# MCU.net
KiCad netlist of a schematic drawn in Altium Designer
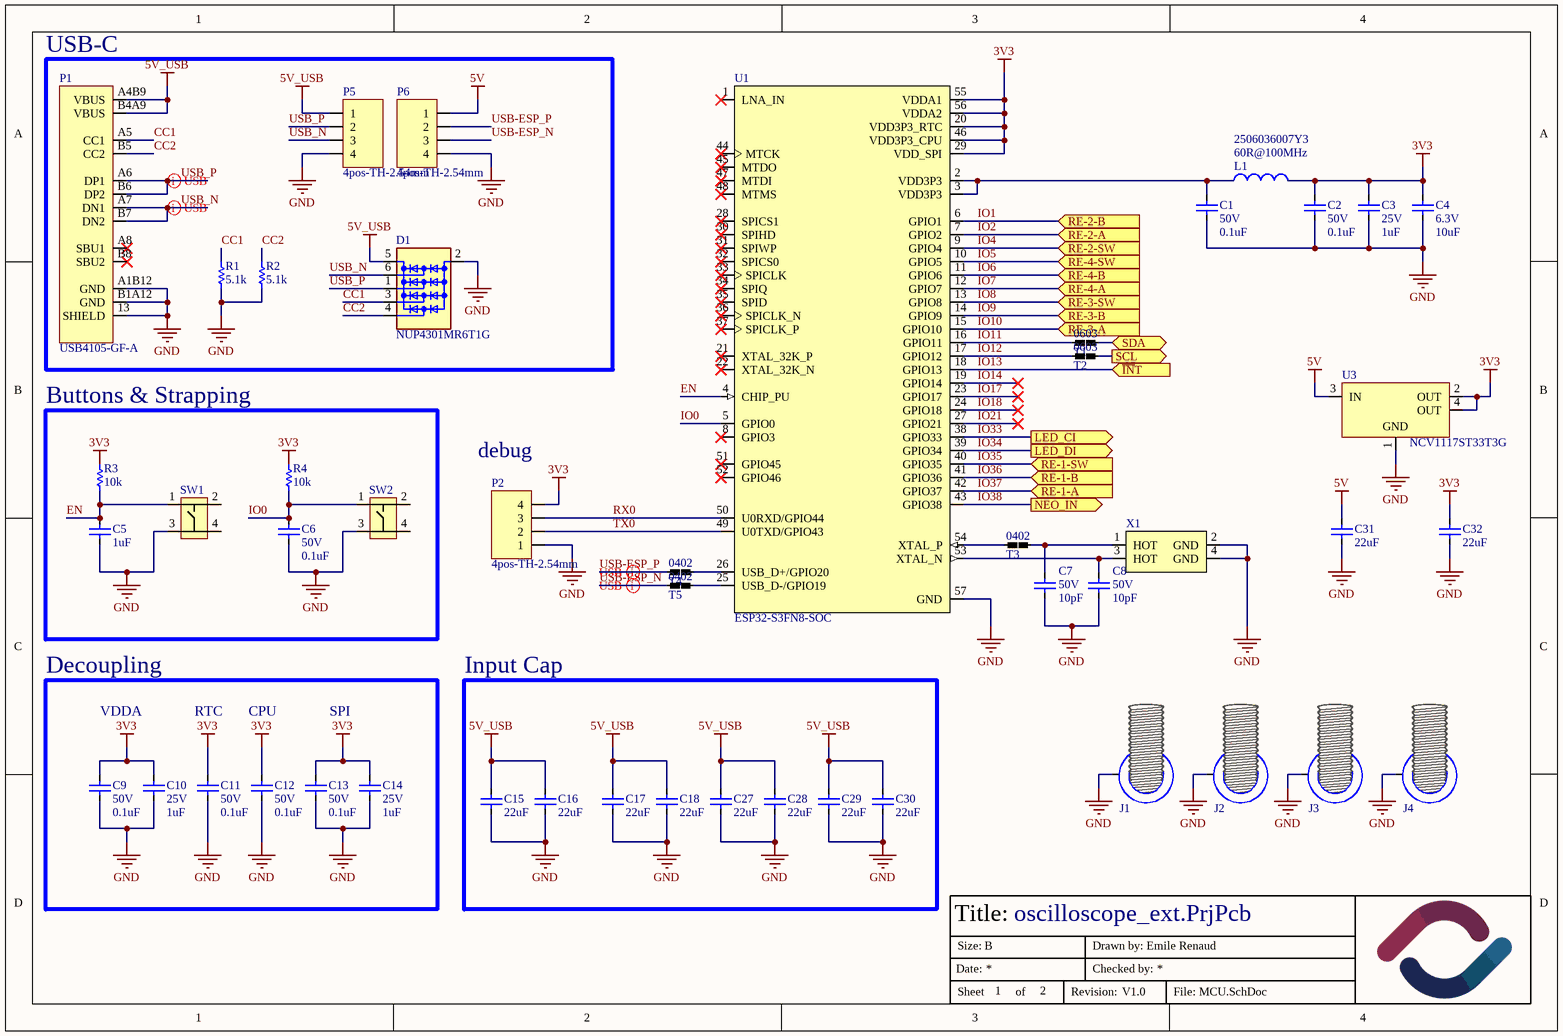
[diagram p0: MCU.SchDoc]

(export (version "E")
  (design (tool "Eeschema 10.0.6"))
  (components
    (comp (ref "C1")
      (value "0.1uF")
      (footprint "CAPACITOR-0603")
      (description "Capacitor-0603-0.1uF-50V-X7R")
      (fields (field (name "VOLT") "50V"))
      (libsource (lib "Capacitors") (part "Capacitor-0603-0.1uF-50V-X7R"))
    )
    (comp (ref "C2")
      (value "0.1uF")
      (footprint "CAPACITOR-0603")
      (description "Capacitor-0603-0.1uF-50V-X7R")
      (fields (field (name "VOLT") "50V"))
      (libsource (lib "Capacitors") (part "Capacitor-0603-0.1uF-50V-X7R"))
    )
    (comp (ref "C3")
      (value "1uF")
      (footprint "CAPACITOR-0603")
      (description "Capacitor-0603-1uF-25V-X5R")
      (fields (field (name "VOLT") "25V"))
      (libsource (lib "Capacitors") (part "Capacitor-0603-1uF-25V-X5R"))
    )
    (comp (ref "C4")
      (value "10uF")
      (footprint "CAPACITOR-0603")
      (description "Capacitor-0603-10uF-6.3V-X5R, Low ESR, Low ESL")
      (fields (field (name "VOLT") "6.3V") (field (name "Comment") "Capacitor-0603-10uF-6.3V-X5R"))
      (libsource (lib "Capacitors") (part "Capacitor-0603-10uF-6.3V-X5R"))
    )
    (comp (ref "C5")
      (value "1uF")
      (footprint "CAPACITOR-0603")
      (description "Capacitor-0603-1uF-25V-X5R")
      (libsource (lib "Capacitors") (part "Capacitor-0603-1uF-25V-X5R"))
    )
    (comp (ref "C6")
      (value "0.1uF")
      (footprint "CAPACITOR-0603")
      (description "Capacitor-0603-0.1uF-50V-X7R")
      (fields (field (name "VOLT") "50V"))
      (libsource (lib "Capacitors") (part "Capacitor-0603-0.1uF-50V-X7R"))
    )
    (comp (ref "C7")
      (value "10pF")
      (footprint "CAPACITOR-0402")
      (description "Capacitor-0402-10pF-50V-C0G")
      (fields (field (name "VOLT") "50V"))
      (libsource (lib "Capacitors") (part "Capacitor-0402-10pF-50V-C0G"))
    )
    (comp (ref "C8")
      (value "10pF")
      (footprint "CAPACITOR-0402")
      (description "Capacitor-0402-10pF-50V-C0G")
      (fields (field (name "VOLT") "50V"))
      (libsource (lib "Capacitors") (part "Capacitor-0402-10pF-50V-C0G"))
    )
    (comp (ref "C9")
      (value "0.1uF")
      (footprint "CAPACITOR-0603")
      (description "Capacitor-0603-0.1uF-50V-X7R")
      (fields (field (name "VOLT") "50V"))
      (libsource (lib "Capacitors") (part "Capacitor-0603-0.1uF-50V-X7R"))
    )
    (comp (ref "C10")
      (value "1uF")
      (footprint "CAPACITOR-0603")
      (description "Capacitor-0603-1uF-25V-X5R")
      (fields (field (name "VOLT") "25V"))
      (libsource (lib "Capacitors") (part "Capacitor-0603-1uF-25V-X5R"))
    )
    (comp (ref "C11")
      (value "0.1uF")
      (footprint "CAPACITOR-0603")
      (description "Capacitor-0603-0.1uF-50V-X7R")
      (fields (field (name "VOLT") "50V"))
      (libsource (lib "Capacitors") (part "Capacitor-0603-0.1uF-50V-X7R"))
    )
    (comp (ref "C12")
      (value "0.1uF")
      (footprint "CAPACITOR-0603")
      (description "Capacitor-0603-0.1uF-50V-X7R")
      (fields (field (name "VOLT") "50V"))
      (libsource (lib "Capacitors") (part "Capacitor-0603-0.1uF-50V-X7R"))
    )
    (comp (ref "C13")
      (value "0.1uF")
      (footprint "CAPACITOR-0603")
      (description "Capacitor-0603-0.1uF-50V-X7R")
      (fields (field (name "VOLT") "50V"))
      (libsource (lib "Capacitors") (part "Capacitor-0603-0.1uF-50V-X7R"))
    )
    (comp (ref "C14")
      (value "1uF")
      (footprint "CAPACITOR-0603")
      (description "Capacitor-0603-1uF-25V-X5R")
      (fields (field (name "VOLT") "25V"))
      (libsource (lib "Capacitors") (part "Capacitor-0603-1uF-25V-X5R"))
    )
    (comp (ref "C15")
      (value "22uF")
      (footprint "CAPACITOR-0805")
      (description "Capacitor-0805-22uF-16V-X5R")
      (libsource (lib "Capacitors") (part "Capacitor-0805-22uF-16V-X5R"))
    )
    (comp (ref "C16")
      (value "22uF")
      (footprint "CAPACITOR-0805")
      (description "Capacitor-0805-22uF-16V-X5R")
      (libsource (lib "Capacitors") (part "Capacitor-0805-22uF-16V-X5R"))
    )
    (comp (ref "C17")
      (value "22uF")
      (footprint "CAPACITOR-0805")
      (description "Capacitor-0805-22uF-16V-X5R")
      (libsource (lib "Capacitors") (part "Capacitor-0805-22uF-16V-X5R"))
    )
    (comp (ref "C18")
      (value "22uF")
      (footprint "CAPACITOR-0805")
      (description "Capacitor-0805-22uF-16V-X5R")
      (libsource (lib "Capacitors") (part "Capacitor-0805-22uF-16V-X5R"))
    )
    (comp (ref "C27")
      (value "22uF")
      (footprint "CAPACITOR-0805")
      (description "Capacitor-0805-22uF-16V-X5R")
      (libsource (lib "Capacitors") (part "Capacitor-0805-22uF-16V-X5R"))
    )
    (comp (ref "C28")
      (value "22uF")
      (footprint "CAPACITOR-0805")
      (description "Capacitor-0805-22uF-16V-X5R")
      (libsource (lib "Capacitors") (part "Capacitor-0805-22uF-16V-X5R"))
    )
    (comp (ref "C29")
      (value "22uF")
      (footprint "CAPACITOR-0805")
      (description "Capacitor-0805-22uF-16V-X5R")
      (libsource (lib "Capacitors") (part "Capacitor-0805-22uF-16V-X5R"))
    )
    (comp (ref "C30")
      (value "22uF")
      (footprint "CAPACITOR-0805")
      (description "Capacitor-0805-22uF-16V-X5R")
      (libsource (lib "Capacitors") (part "Capacitor-0805-22uF-16V-X5R"))
    )
    (comp (ref "C31")
      (value "22uF")
      (footprint "CAPACITOR-0805")
      (description "Capacitor-0805-22uF-16V-X5R")
      (libsource (lib "Capacitors") (part "Capacitor-0805-22uF-16V-X5R"))
    )
    (comp (ref "C32")
      (value "22uF")
      (footprint "CAPACITOR-0805")
      (description "Capacitor-0805-22uF-16V-X5R")
      (libsource (lib "Capacitors") (part "Capacitor-0805-22uF-16V-X5R"))
    )
    (comp (ref "D1")
      (value "NUP4301MR6T1G")
      (footprint "SOT-23-6")
      (description "4CH Clamp Ipp Tvs Diode Surface Mount SOT23-6 (SC74)")
      (libsource (lib "diodes") (part "NUP4301MR6T1G"))
    )
    (comp (ref "J1")
      (value "hole")
      (footprint "HOLE-3.40MM-M3-8MMEYELET")
      (description "Hole for M3 Bolt with 8mm pad")
      (libsource (lib "JumpersAndHoles") (part "Hole 3.40mm M3-Eyelet"))
    )
    (comp (ref "J2")
      (value "hole")
      (footprint "HOLE-3.40MM-M3-8MMEYELET")
      (description "Hole for M3 Bolt with 8mm pad")
      (libsource (lib "JumpersAndHoles") (part "Hole 3.40mm M3-Eyelet"))
    )
    (comp (ref "J3")
      (value "hole")
      (footprint "HOLE-3.40MM-M3-8MMEYELET")
      (description "Hole for M3 Bolt with 8mm pad")
      (libsource (lib "JumpersAndHoles") (part "Hole 3.40mm M3-Eyelet"))
    )
    (comp (ref "J4")
      (value "hole")
      (footprint "HOLE-3.40MM-M3-8MMEYELET")
      (description "Hole for M3 Bolt with 8mm pad")
      (libsource (lib "JumpersAndHoles") (part "Hole 3.40mm M3-Eyelet"))
    )
    (comp (ref "L1")
      (value "2506036007Y3")
      (footprint "CAPACITOR-0603")
      (description "60 Ohms @ 100 MHz 1 Signal Line Ferrite Bead 0603 (1608 Metric) 3A 40mOhm")
      (fields (field (name "ALTIUM_VALUE") "60R@100MHz"))
      (libsource (lib "Inductors") (part "2506036007Y3"))
    )
    (comp (ref "P1")
      (value "USB4105-GF-A")
      (footprint "USB-C")
      (description "CONN RCP USB2.0 TYP C 24P SMD RA\r\n5A")
      (libsource (lib "PC-connector") (part "USB4105-GF-A"))
    )
    (comp (ref "P2")
      (value "4pos-TH-2.54mm")
      (footprint "HDR1X4")
      (description "4pos TH 2.54mm Header")
      (libsource (lib "") (part "4pos-TH-2.54mm_1"))
    )
    (comp (ref "P5")
      (value "4pos-TH-2.54mm")
      (footprint "HDR1X4")
      (description "4pos TH 2.54mm Header")
      (libsource (lib "Header") (part "4pos-TH-2.54mm"))
    )
    (comp (ref "P6")
      (value "4pos-TH-2.54mm")
      (footprint "HDR1X4")
      (description "4pos TH 2.54mm Header")
      (libsource (lib "") (part "4pos-TH-2.54mm_2"))
    )
    (comp (ref "R1")
      (value "5.1k")
      (footprint "RESISTOR-0603")
      (description "0603 footprint DO NOT INSTALL")
      (fields (field (name "Comment") "Resistor-0603-5.1k"))
      (libsource (lib "Resistors") (part "Resistor-0603-DNI"))
    )
    (comp (ref "R2")
      (value "5.1k")
      (footprint "RESISTOR-0603")
      (description "0603 footprint DO NOT INSTALL")
      (fields (field (name "Comment") "Resistor-0603-5.1k"))
      (libsource (lib "Resistors") (part "Resistor-0603-DNI"))
    )
    (comp (ref "R3")
      (value "10k")
      (footprint "Resistor-0603")
      (description "Resistor0603-10k")
      (fields (field (name "Comment") "SMT resistor"))
      (libsource (lib "Resistors") (part "Resistor0603-10k"))
    )
    (comp (ref "R4")
      (value "10k")
      (footprint "Resistor-0603")
      (description "Resistor0603-10k")
      (fields (field (name "Comment") "SMT resistor"))
      (libsource (lib "Resistors") (part "Resistor0603-10k"))
    )
    (comp (ref "SW1")
      (value "PTS815 SJM 250 SMTR LFS")
      (footprint "SW4_PTS815 SJM 250 SMTR LFS_CNK")
      (description "TACT 4.2 X 3.2, 2.5 MM H, 180GF,")
      (libsource (lib "THTPushButtonSwitches") (part "PTS815 SJM 250 SMTR LFS"))
    )
    (comp (ref "SW2")
      (value "PTS815 SJM 250 SMTR LFS")
      (footprint "SW4_PTS815 SJM 250 SMTR LFS_CNK")
      (description "TACT 4.2 X 3.2, 2.5 MM H, 180GF,")
      (libsource (lib "THTPushButtonSwitches") (part "PTS815 SJM 250 SMTR LFS"))
    )
    (comp (ref "T1")
      (value "NetTie_0603")
      (footprint "NetTie-0603-short")
      (libsource (lib "JumpersAndHoles") (part "NetTie_0603"))
    )
    (comp (ref "T2")
      (value "NetTie_0603")
      (footprint "NetTie-0603-short")
      (libsource (lib "JumpersAndHoles") (part "NetTie_0603"))
    )
    (comp (ref "T3")
      (value "NetTie_0402")
      (footprint "NetTie-0402")
      (libsource (lib "JumpersAndHoles") (part "NetTie_0402"))
    )
    (comp (ref "T4")
      (value "NetTie_0402")
      (footprint "NetTie-0402")
      (libsource (lib "JumpersAndHoles") (part "NetTie_0402"))
    )
    (comp (ref "T5")
      (value "NetTie_0402")
      (footprint "NetTie-0402")
      (libsource (lib "JumpersAndHoles") (part "NetTie_0402"))
    )
    (comp (ref "U1")
      (value "ESP32-S3FN8-SOC")
      (footprint "VFQFN-56 Exposed Pad")
      (fields (field (name "MF") "Espressif Systems") (field (name "MP") "ESP32-S3FN8"))
      (libsource (lib "Microcontrollers") (part "ESP32-S3FN8-SOC"))
    )
    (comp (ref "U3")
      (value "NCV1117ST33T3G")
      (footprint "SOT-223-3/TO-261-3S")
      (description "IC REG LINEAR 3.3V 1A SOT223")
      (libsource (lib "PMIC-VoltageRegulators-LinearRegulators") (part "NCV1117ST33T3G"))
    )
    (comp (ref "X1")
      (value "CX2016DB40000D0FLJCC")
      (footprint "4-SMD")
      (description "40 MHz ±10ppm Crystal 8pF 50 Ohms 4-SMD, No Lead")
      (libsource (lib "Crystals") (part "CX2016DB40000D0FLJCC"))
    )
  )
  (nets
    (net (code "1") (name "/CC1") (class "Default")
      (node (ref "D1") (pin "3") (pinfunction "L3_3") (pintype "passive"))
      (node (ref "P1") (pin "A5") (pinfunction "CC1_A5") (pintype "passive"))
      (node (ref "R1") (pin "2") (pinfunction "2_2") (pintype "passive"))
    )
    (net (code "2") (name "/CC2") (class "Default")
      (node (ref "D1") (pin "4") (pinfunction "L4_4") (pintype "passive"))
      (node (ref "P1") (pin "B5") (pinfunction "CC2_B5") (pintype "passive"))
      (node (ref "R2") (pin "2") (pinfunction "2_2") (pintype "passive"))
    )
    (net (code "3") (name "/EN") (class "Default")
      (node (ref "C5") (pin "2") (pinfunction "2_2") (pintype "passive"))
      (node (ref "R3") (pin "1") (pinfunction "1_1") (pintype "passive"))
      (node (ref "SW1") (pin "1") (pinfunction "1_1") (pintype "passive"))
      (node (ref "U1") (pin "4") (pinfunction "CHIP_PU_4") (pintype "input"))
    )
    (net (code "4") (name "/IO0") (class "Default")
      (node (ref "C6") (pin "2") (pinfunction "2_2") (pintype "passive"))
      (node (ref "R4") (pin "1") (pinfunction "1_1") (pintype "passive"))
      (node (ref "SW2") (pin "1") (pinfunction "1_1") (pintype "passive"))
      (node (ref "U1") (pin "5") (pinfunction "GPIO0_5") (pintype "bidirectional"))
    )
    (net (code "5") (name "/IO1") (class "Default")
      (node (ref "U1") (pin "6") (pinfunction "GPIO1_6") (pintype "bidirectional"))
    )
    (net (code "6") (name "/IO2") (class "Default")
      (node (ref "U1") (pin "7") (pinfunction "GPIO2_7") (pintype "bidirectional"))
    )
    (net (code "7") (name "/IO4") (class "Default")
      (node (ref "U1") (pin "9") (pinfunction "GPIO4_9") (pintype "bidirectional"))
    )
    (net (code "8") (name "/IO5") (class "Default")
      (node (ref "U1") (pin "10") (pinfunction "GPIO5_10") (pintype "bidirectional"))
    )
    (net (code "9") (name "/IO6") (class "Default")
      (node (ref "U1") (pin "11") (pinfunction "GPIO6_11") (pintype "bidirectional"))
    )
    (net (code "10") (name "/IO7") (class "Default")
      (node (ref "U1") (pin "12") (pinfunction "GPIO7_12") (pintype "bidirectional"))
    )
    (net (code "11") (name "/IO8") (class "Default")
      (node (ref "U1") (pin "13") (pinfunction "GPIO8_13") (pintype "bidirectional"))
    )
    (net (code "12") (name "/IO9") (class "Default")
      (node (ref "U1") (pin "14") (pinfunction "GPIO9_14") (pintype "bidirectional"))
    )
    (net (code "13") (name "/IO10") (class "Default")
      (node (ref "U1") (pin "15") (pinfunction "GPIO10_15") (pintype "bidirectional"))
    )
    (net (code "14") (name "/IO11") (class "Default")
      (node (ref "T1") (pin "2") (pinfunction "2_2") (pintype "passive"))
      (node (ref "U1") (pin "16") (pinfunction "GPIO11_16") (pintype "bidirectional"))
    )
    (net (code "15") (name "/IO12") (class "Default")
      (node (ref "T2") (pin "2") (pinfunction "2_2") (pintype "passive"))
      (node (ref "U1") (pin "17") (pinfunction "GPIO12_17") (pintype "bidirectional"))
    )
    (net (code "16") (name "/IO13") (class "Default")
      (node (ref "U1") (pin "18") (pinfunction "GPIO13_18") (pintype "bidirectional"))
    )
    (net (code "17") (name "/IO14") (class "Default")
      (node (ref "U1") (pin "19") (pinfunction "GPIO14_19") (pintype "bidirectional+no_connect"))
    )
    (net (code "18") (name "/IO17") (class "Default")
      (node (ref "U1") (pin "23") (pinfunction "GPIO17_23") (pintype "bidirectional+no_connect"))
    )
    (net (code "19") (name "/IO18") (class "Default")
      (node (ref "U1") (pin "24") (pinfunction "GPIO18_24") (pintype "bidirectional+no_connect"))
    )
    (net (code "20") (name "/IO21") (class "Default")
      (node (ref "U1") (pin "27") (pinfunction "GPIO21_27") (pintype "bidirectional+no_connect"))
    )
    (net (code "21") (name "/IO33") (class "Default")
      (node (ref "U1") (pin "38") (pinfunction "GPIO33_38") (pintype "bidirectional"))
    )
    (net (code "22") (name "/IO34") (class "Default")
      (node (ref "U1") (pin "39") (pinfunction "GPIO34_39") (pintype "bidirectional"))
    )
    (net (code "23") (name "/IO35") (class "Default")
      (node (ref "U1") (pin "40") (pinfunction "GPIO35_40") (pintype "bidirectional"))
    )
    (net (code "24") (name "/IO36") (class "Default")
      (node (ref "U1") (pin "41") (pinfunction "GPIO36_41") (pintype "bidirectional"))
    )
    (net (code "25") (name "/IO37") (class "Default")
      (node (ref "U1") (pin "42") (pinfunction "GPIO37_42") (pintype "bidirectional"))
    )
    (net (code "26") (name "/IO38") (class "Default")
      (node (ref "U1") (pin "43") (pinfunction "GPIO38_43") (pintype "bidirectional"))
    )
    (net (code "27") (name "/RX0") (class "Default")
      (node (ref "P2") (pin "3") (pinfunction "3_3") (pintype "passive"))
      (node (ref "U1") (pin "50") (pinfunction "U0RXD/GPIO44_50") (pintype "bidirectional"))
    )
    (net (code "28") (name "/SCL") (class "Default")
      (node (ref "T2") (pin "1") (pinfunction "1_1") (pintype "passive"))
    )
    (net (code "29") (name "/SDA") (class "Default")
      (node (ref "T1") (pin "1") (pinfunction "1_1") (pintype "passive"))
    )
    (net (code "30") (name "/TX0") (class "Default")
      (node (ref "P2") (pin "2") (pinfunction "2_2") (pintype "passive"))
      (node (ref "U1") (pin "49") (pinfunction "U0TXD/GPIO43_49") (pintype "bidirectional"))
    )
    (net (code "31") (name "/USB-ESP_N") (class "Default")
      (node (ref "P6") (pin "3") (pinfunction "3_3") (pintype "passive"))
      (node (ref "T5") (pin "2") (pinfunction "2_2") (pintype "passive"))
    )
    (net (code "32") (name "/USB-ESP_P") (class "Default")
      (node (ref "P6") (pin "2") (pinfunction "2_2") (pintype "passive"))
      (node (ref "T4") (pin "2") (pinfunction "2_2") (pintype "passive"))
    )
    (net (code "33") (name "/USB_N") (class "Default")
      (node (ref "D1") (pin "6") (pinfunction "L1_6") (pintype "passive"))
      (node (ref "P1") (pin "A7") (pinfunction "DN1_A7") (pintype "passive"))
      (node (ref "P1") (pin "B7") (pinfunction "DN2_B7") (pintype "passive"))
      (node (ref "P5") (pin "3") (pinfunction "3_3") (pintype "passive"))
    )
    (net (code "34") (name "/USB_P") (class "Default")
      (node (ref "D1") (pin "1") (pinfunction "L2_1") (pintype "passive"))
      (node (ref "P1") (pin "A6") (pinfunction "DP1_A6") (pintype "passive"))
      (node (ref "P1") (pin "B6") (pinfunction "DP2_B6") (pintype "passive"))
      (node (ref "P5") (pin "2") (pinfunction "2_2") (pintype "passive"))
    )
    (net (code "35") (name "3V3") (class "Default")
      (node (ref "C10") (pin "2") (pinfunction "2_2") (pintype "passive"))
      (node (ref "C11") (pin "2") (pinfunction "2_2") (pintype "passive"))
      (node (ref "C12") (pin "2") (pinfunction "2_2") (pintype "passive"))
      (node (ref "C13") (pin "2") (pinfunction "2_2") (pintype "passive"))
      (node (ref "C14") (pin "2") (pinfunction "2_2") (pintype "passive"))
      (node (ref "C2") (pin "2") (pinfunction "2_2") (pintype "passive"))
      (node (ref "C3") (pin "2") (pinfunction "2_2") (pintype "passive"))
      (node (ref "C32") (pin "2") (pinfunction "2_2") (pintype "passive"))
      (node (ref "C4") (pin "2") (pinfunction "2_2") (pintype "passive"))
      (node (ref "C9") (pin "2") (pinfunction "2_2") (pintype "passive"))
      (node (ref "L1") (pin "2") (pinfunction "2_2") (pintype "passive"))
      (node (ref "P2") (pin "4") (pinfunction "4_4") (pintype "passive"))
      (node (ref "R3") (pin "2") (pinfunction "2_2") (pintype "passive"))
      (node (ref "R4") (pin "2") (pinfunction "2_2") (pintype "passive"))
      (node (ref "U1") (pin "20") (pinfunction "VDD3P3_RTC_20") (pintype "power_in"))
      (node (ref "U1") (pin "29") (pinfunction "VDD_SPI_29") (pintype "power_in"))
      (node (ref "U1") (pin "46") (pinfunction "VDD3P3_CPU_46") (pintype "power_in"))
      (node (ref "U1") (pin "55") (pinfunction "VDDA1_55") (pintype "power_in"))
      (node (ref "U1") (pin "56") (pinfunction "VDDA2_56") (pintype "power_in"))
      (node (ref "U3") (pin "2") (pinfunction "OUT_2") (pintype "passive"))
      (node (ref "U3") (pin "4") (pinfunction "OUT_4") (pintype "passive"))
    )
    (net (code "36") (name "5V") (class "Default")
      (node (ref "C31") (pin "2") (pinfunction "2_2") (pintype "passive"))
      (node (ref "P6") (pin "1") (pinfunction "1_1") (pintype "passive"))
      (node (ref "U3") (pin "3") (pinfunction "IN_3") (pintype "passive"))
    )
    (net (code "37") (name "5V_USB") (class "Default")
      (node (ref "C15") (pin "2") (pinfunction "2_2") (pintype "passive"))
      (node (ref "C16") (pin "2") (pinfunction "2_2") (pintype "passive"))
      (node (ref "C17") (pin "2") (pinfunction "2_2") (pintype "passive"))
      (node (ref "C18") (pin "2") (pinfunction "2_2") (pintype "passive"))
      (node (ref "C27") (pin "2") (pinfunction "2_2") (pintype "passive"))
      (node (ref "C28") (pin "2") (pinfunction "2_2") (pintype "passive"))
      (node (ref "C29") (pin "2") (pinfunction "2_2") (pintype "passive"))
      (node (ref "C30") (pin "2") (pinfunction "2_2") (pintype "passive"))
      (node (ref "D1") (pin "5") (pinfunction "VDD_5") (pintype "passive"))
      (node (ref "P1") (pin "A4B9") (pinfunction "VBUS_A4B9") (pintype "passive"))
      (node (ref "P1") (pin "B4A9") (pinfunction "VBUS_B4A9") (pintype "passive"))
      (node (ref "P5") (pin "1") (pinfunction "1_1") (pintype "passive"))
    )
    (net (code "38") (name "GND") (class "Default")
      (node (ref "C1") (pin "1") (pinfunction "1_1") (pintype "passive"))
      (node (ref "C10") (pin "1") (pinfunction "1_1") (pintype "passive"))
      (node (ref "C11") (pin "1") (pinfunction "1_1") (pintype "passive"))
      (node (ref "C12") (pin "1") (pinfunction "1_1") (pintype "passive"))
      (node (ref "C13") (pin "1") (pinfunction "1_1") (pintype "passive"))
      (node (ref "C14") (pin "1") (pinfunction "1_1") (pintype "passive"))
      (node (ref "C15") (pin "1") (pinfunction "1_1") (pintype "passive"))
      (node (ref "C16") (pin "1") (pinfunction "1_1") (pintype "passive"))
      (node (ref "C17") (pin "1") (pinfunction "1_1") (pintype "passive"))
      (node (ref "C18") (pin "1") (pinfunction "1_1") (pintype "passive"))
      (node (ref "C2") (pin "1") (pinfunction "1_1") (pintype "passive"))
      (node (ref "C27") (pin "1") (pinfunction "1_1") (pintype "passive"))
      (node (ref "C28") (pin "1") (pinfunction "1_1") (pintype "passive"))
      (node (ref "C29") (pin "1") (pinfunction "1_1") (pintype "passive"))
      (node (ref "C3") (pin "1") (pinfunction "1_1") (pintype "passive"))
      (node (ref "C30") (pin "1") (pinfunction "1_1") (pintype "passive"))
      (node (ref "C31") (pin "1") (pinfunction "1_1") (pintype "passive"))
      (node (ref "C32") (pin "1") (pinfunction "1_1") (pintype "passive"))
      (node (ref "C4") (pin "1") (pinfunction "1_1") (pintype "passive"))
      (node (ref "C5") (pin "1") (pinfunction "1_1") (pintype "passive"))
      (node (ref "C6") (pin "1") (pinfunction "1_1") (pintype "passive"))
      (node (ref "C7") (pin "1") (pinfunction "1_1") (pintype "passive"))
      (node (ref "C8") (pin "1") (pinfunction "1_1") (pintype "passive"))
      (node (ref "C9") (pin "1") (pinfunction "1_1") (pintype "passive"))
      (node (ref "D1") (pin "2") (pinfunction "GND_2") (pintype "passive"))
      (node (ref "J1") (pin "1") (pinfunction "1_1") (pintype "passive"))
      (node (ref "J2") (pin "1") (pinfunction "1_1") (pintype "passive"))
      (node (ref "J3") (pin "1") (pinfunction "1_1") (pintype "passive"))
      (node (ref "J4") (pin "1") (pinfunction "1_1") (pintype "passive"))
      (node (ref "P1") (pin "13") (pinfunction "SHIELD_13") (pintype "passive"))
      (node (ref "P1") (pin "A1B12") (pinfunction "GND_A1B12") (pintype "passive"))
      (node (ref "P1") (pin "B1A12") (pinfunction "GND_B1A12") (pintype "passive"))
      (node (ref "P2") (pin "1") (pinfunction "1_1") (pintype "passive"))
      (node (ref "P5") (pin "4") (pinfunction "4_4") (pintype "passive"))
      (node (ref "P6") (pin "4") (pinfunction "4_4") (pintype "passive"))
      (node (ref "R1") (pin "1") (pinfunction "1_1") (pintype "passive"))
      (node (ref "R2") (pin "1") (pinfunction "1_1") (pintype "passive"))
      (node (ref "SW1") (pin "3") (pinfunction "3_3") (pintype "passive"))
      (node (ref "SW2") (pin "3") (pinfunction "3_3") (pintype "passive"))
      (node (ref "U1") (pin "57") (pinfunction "GND_57") (pintype "power_in"))
      (node (ref "U3") (pin "1") (pinfunction "GND_1") (pintype "passive"))
      (node (ref "X1") (pin "2") (pinfunction "GND_2") (pintype "passive"))
      (node (ref "X1") (pin "4") (pinfunction "GND_4") (pintype "passive"))
    )
    (net (code "39") (name "Net-(C1-Pad2)") (class "Default")
      (node (ref "C1") (pin "2") (pinfunction "2_2") (pintype "passive"))
      (node (ref "L1") (pin "1") (pinfunction "1_1") (pintype "passive"))
      (node (ref "U1") (pin "2") (pinfunction "VDD3P3_2") (pintype "power_in"))
      (node (ref "U1") (pin "3") (pinfunction "VDD3P3_3") (pintype "power_in"))
    )
    (net (code "40") (name "Net-(C7-Pad2)") (class "Default")
      (node (ref "C7") (pin "2") (pinfunction "2_2") (pintype "passive"))
      (node (ref "T3") (pin "1") (pinfunction "1_1") (pintype "passive"))
      (node (ref "X1") (pin "1") (pinfunction "HOT_1") (pintype "passive"))
    )
    (net (code "41") (name "Net-(U1-USB_D+{slash}GPIO20)") (class "Default")
      (node (ref "T4") (pin "1") (pinfunction "1_1") (pintype "passive"))
      (node (ref "U1") (pin "26") (pinfunction "USB_D+/GPIO20_26") (pintype "bidirectional"))
    )
    (net (code "42") (name "Net-(U1-USB_D-{slash}GPIO19)") (class "Default")
      (node (ref "T5") (pin "1") (pinfunction "1_1") (pintype "passive"))
      (node (ref "U1") (pin "25") (pinfunction "USB_D-/GPIO19_25") (pintype "bidirectional"))
    )
    (net (code "43") (name "Net-(U1-XTAL_N)") (class "Default")
      (node (ref "C8") (pin "2") (pinfunction "2_2") (pintype "passive"))
      (node (ref "U1") (pin "53") (pinfunction "XTAL_N_53") (pintype "output"))
      (node (ref "X1") (pin "3") (pinfunction "HOT_3") (pintype "passive"))
    )
    (net (code "44") (name "Net-(U1-XTAL_P)") (class "Default")
      (node (ref "T3") (pin "2") (pinfunction "2_2") (pintype "passive"))
      (node (ref "U1") (pin "54") (pinfunction "XTAL_P_54") (pintype "input"))
    )
    (net (code "45") (name "unconnected-(P1-SBU1-PadA8)") (class "Default")
      (node (ref "P1") (pin "A8") (pinfunction "SBU1_A8") (pintype "passive+no_connect"))
    )
    (net (code "46") (name "unconnected-(P1-SBU2-PadB8)") (class "Default")
      (node (ref "P1") (pin "B8") (pinfunction "SBU2_B8") (pintype "passive+no_connect"))
    )
    (net (code "47") (name "unconnected-(SW1-Pad2)") (class "Default")
      (node (ref "SW1") (pin "2") (pinfunction "2_2") (pintype "passive"))
    )
    (net (code "48") (name "unconnected-(SW1-Pad4)") (class "Default")
      (node (ref "SW1") (pin "4") (pinfunction "4_4") (pintype "passive"))
    )
    (net (code "49") (name "unconnected-(SW2-Pad2)") (class "Default")
      (node (ref "SW2") (pin "2") (pinfunction "2_2") (pintype "passive"))
    )
    (net (code "50") (name "unconnected-(SW2-Pad4)") (class "Default")
      (node (ref "SW2") (pin "4") (pinfunction "4_4") (pintype "passive"))
    )
    (net (code "51") (name "unconnected-(U1-GPIO3-Pad8)") (class "Default")
      (node (ref "U1") (pin "8") (pinfunction "GPIO3_8") (pintype "bidirectional+no_connect"))
    )
    (net (code "52") (name "unconnected-(U1-GPIO45-Pad51)") (class "Default")
      (node (ref "U1") (pin "51") (pinfunction "GPIO45_51") (pintype "bidirectional+no_connect"))
    )
    (net (code "53") (name "unconnected-(U1-GPIO46-Pad52)") (class "Default")
      (node (ref "U1") (pin "52") (pinfunction "GPIO46_52") (pintype "bidirectional+no_connect"))
    )
    (net (code "54") (name "unconnected-(U1-LNA_IN-Pad1)") (class "Default")
      (node (ref "U1") (pin "1") (pinfunction "LNA_IN_1") (pintype "bidirectional+no_connect"))
    )
    (net (code "55") (name "unconnected-(U1-MTCK-Pad44)") (class "Default")
      (node (ref "U1") (pin "44") (pinfunction "MTCK_44") (pintype "bidirectional+no_connect"))
    )
    (net (code "56") (name "unconnected-(U1-MTDI-Pad47)") (class "Default")
      (node (ref "U1") (pin "47") (pinfunction "MTDI_47") (pintype "bidirectional+no_connect"))
    )
    (net (code "57") (name "unconnected-(U1-MTDO-Pad45)") (class "Default")
      (node (ref "U1") (pin "45") (pinfunction "MTDO_45") (pintype "bidirectional+no_connect"))
    )
    (net (code "58") (name "unconnected-(U1-MTMS-Pad48)") (class "Default")
      (node (ref "U1") (pin "48") (pinfunction "MTMS_48") (pintype "bidirectional+no_connect"))
    )
    (net (code "59") (name "unconnected-(U1-SPICLK-Pad33)") (class "Default")
      (node (ref "U1") (pin "33") (pinfunction "SPICLK_33") (pintype "bidirectional+no_connect"))
    )
    (net (code "60") (name "unconnected-(U1-SPICLK_N-Pad36)") (class "Default")
      (node (ref "U1") (pin "36") (pinfunction "SPICLK_N_36") (pintype "bidirectional+no_connect"))
    )
    (net (code "61") (name "unconnected-(U1-SPICLK_P-Pad37)") (class "Default")
      (node (ref "U1") (pin "37") (pinfunction "SPICLK_P_37") (pintype "bidirectional+no_connect"))
    )
    (net (code "62") (name "unconnected-(U1-SPICS0-Pad32)") (class "Default")
      (node (ref "U1") (pin "32") (pinfunction "SPICS0_32") (pintype "bidirectional+no_connect"))
    )
    (net (code "63") (name "unconnected-(U1-SPICS1-Pad28)") (class "Default")
      (node (ref "U1") (pin "28") (pinfunction "SPICS1_28") (pintype "bidirectional+no_connect"))
    )
    (net (code "64") (name "unconnected-(U1-SPID-Pad35)") (class "Default")
      (node (ref "U1") (pin "35") (pinfunction "SPID_35") (pintype "bidirectional+no_connect"))
    )
    (net (code "65") (name "unconnected-(U1-SPIHD-Pad30)") (class "Default")
      (node (ref "U1") (pin "30") (pinfunction "SPIHD_30") (pintype "bidirectional+no_connect"))
    )
    (net (code "66") (name "unconnected-(U1-SPIQ-Pad34)") (class "Default")
      (node (ref "U1") (pin "34") (pinfunction "SPIQ_34") (pintype "bidirectional+no_connect"))
    )
    (net (code "67") (name "unconnected-(U1-SPIWP-Pad31)") (class "Default")
      (node (ref "U1") (pin "31") (pinfunction "SPIWP_31") (pintype "bidirectional+no_connect"))
    )
    (net (code "68") (name "unconnected-(U1-XTAL_32K_N-Pad22)") (class "Default")
      (node (ref "U1") (pin "22") (pinfunction "XTAL_32K_N_22") (pintype "bidirectional+no_connect"))
    )
    (net (code "69") (name "unconnected-(U1-XTAL_32K_P-Pad21)") (class "Default")
      (node (ref "U1") (pin "21") (pinfunction "XTAL_32K_P_21") (pintype "bidirectional+no_connect"))
    )
  )
)
